# EBN_SBAT_V03A.net
KiCad netlist of a schematic drawn in EAGLE
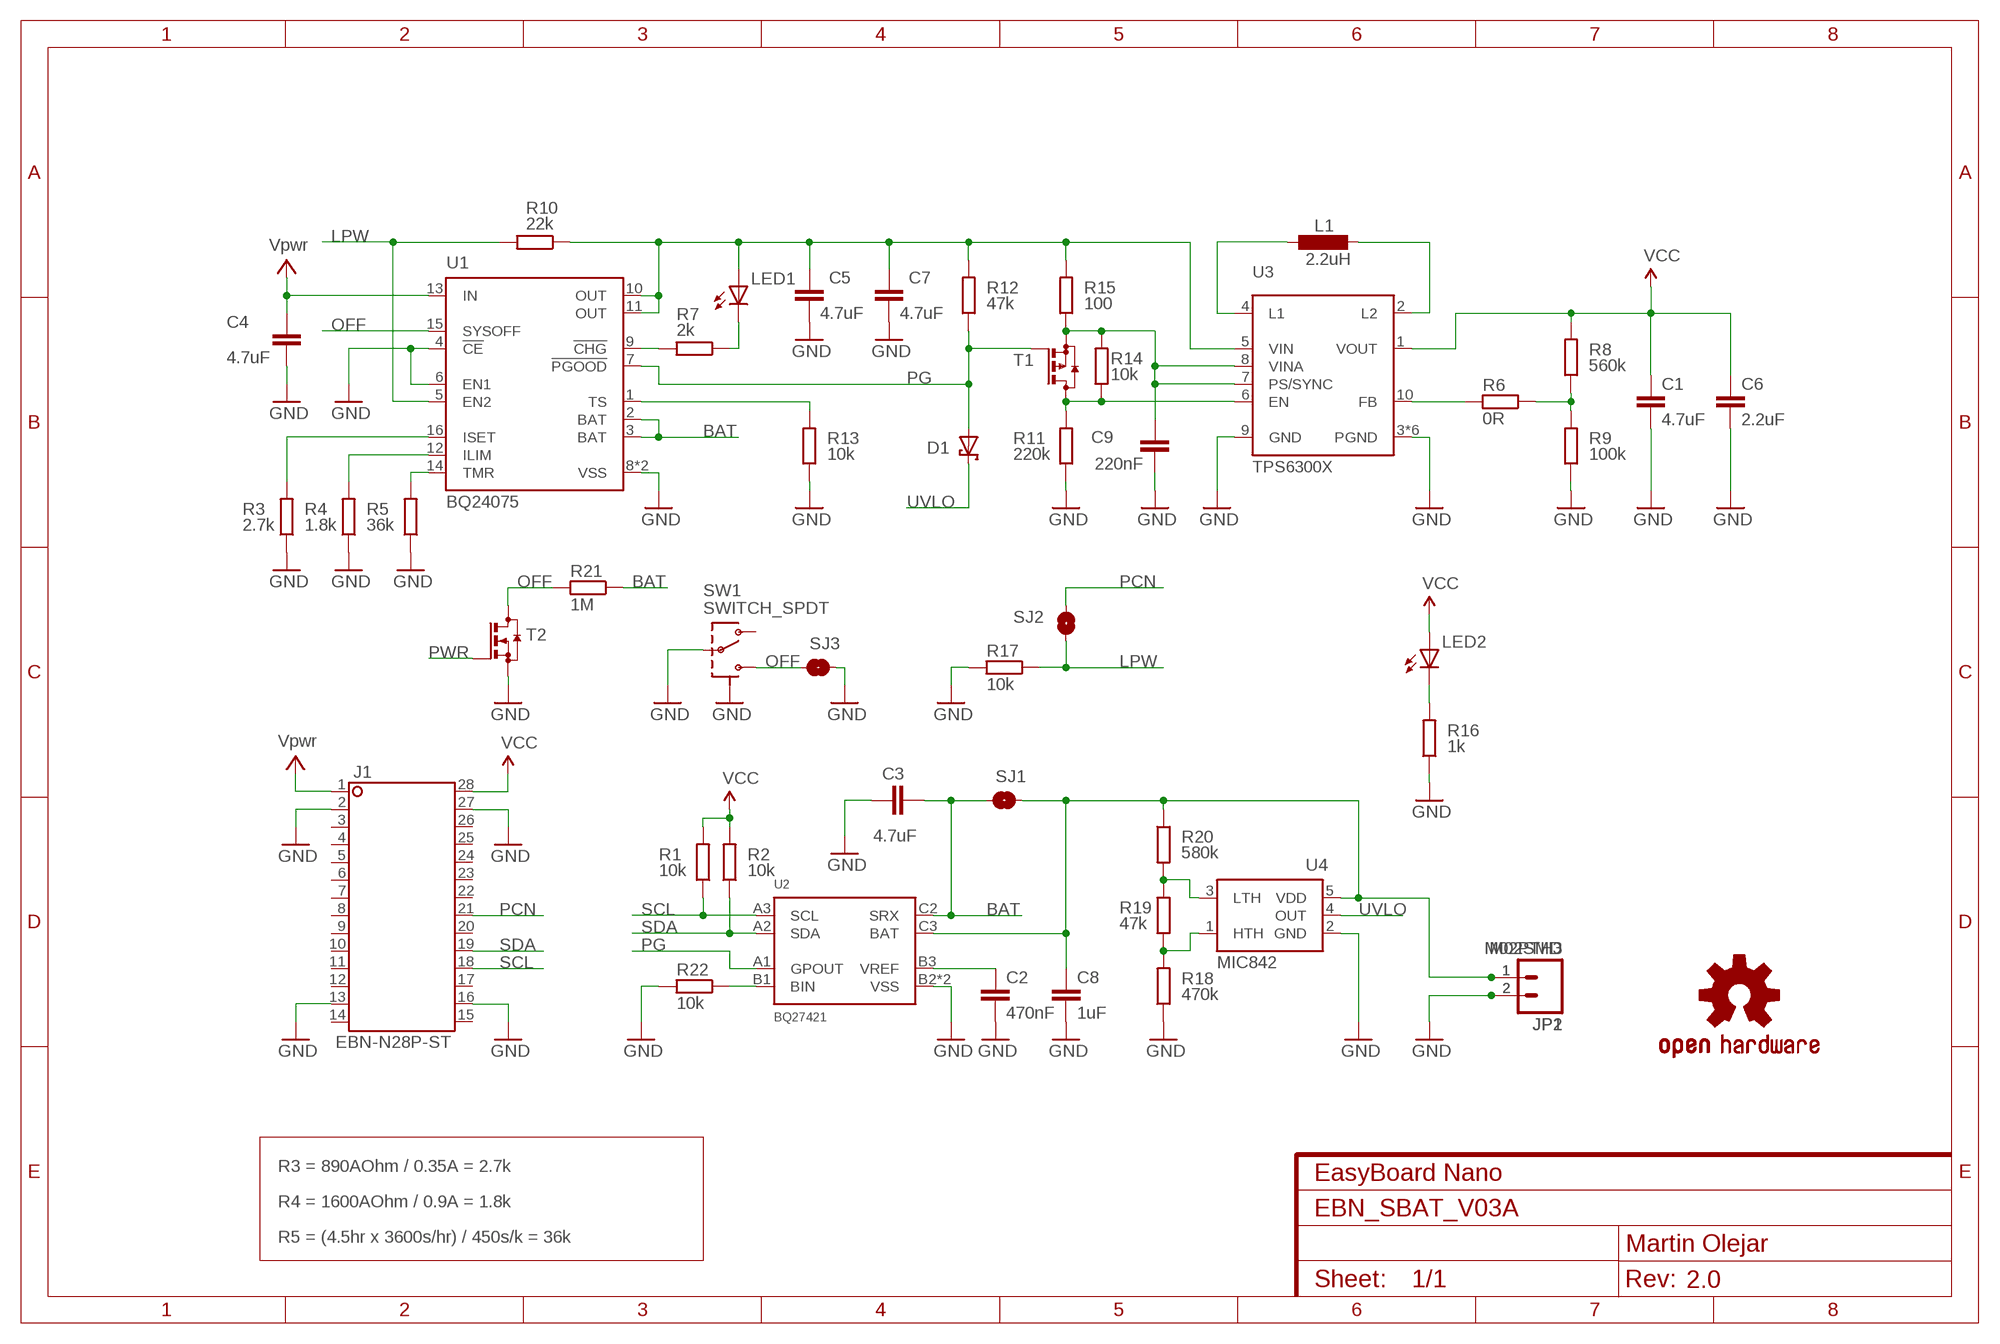
[diagram p0: schematic, sheet 1]

(export (version "E")
  (design (tool "Eeschema 10.0.6"))
  (components
    (comp (ref "C1")
      (value "4.7uF")
      (footprint "eagle-import:C0603")
      (libsource (lib "eagle-import") (part "C-EUC0603"))
    )
    (comp (ref "C2")
      (value "470nF")
      (footprint "eagle-import:C0402")
      (libsource (lib "eagle-import") (part "C-EUC0402"))
    )
    (comp (ref "C3")
      (value "4.7uF")
      (footprint "eagle-import:C0805")
      (libsource (lib "eagle-import") (part "C-EUC0805"))
    )
    (comp (ref "C4")
      (value "4.7uF")
      (footprint "eagle-import:C0603")
      (libsource (lib "eagle-import") (part "C-EUC0603"))
    )
    (comp (ref "C5")
      (value "4.7uF")
      (footprint "eagle-import:C0603")
      (libsource (lib "eagle-import") (part "C-EUC0603"))
    )
    (comp (ref "C6")
      (value "2.2uF")
      (footprint "eagle-import:C0603")
      (libsource (lib "eagle-import") (part "C-EUC0603"))
    )
    (comp (ref "C7")
      (value "4.7uF")
      (footprint "eagle-import:C0603")
      (libsource (lib "eagle-import") (part "C-EUC0603"))
    )
    (comp (ref "C8")
      (value "1uF")
      (footprint "eagle-import:C0402")
      (libsource (lib "eagle-import") (part "C-EUC0402"))
    )
    (comp (ref "C9")
      (value "220nF")
      (footprint "eagle-import:C0402")
      (libsource (lib "eagle-import") (part "C-EUC0402"))
    )
    (comp (ref "D1")
      (value "-SHOTTKY-SOD323_ST")
      (footprint "eagle-import:SOD323_ST")
      (libsource (lib "eagle-import") (part "-SHOTTKY-SOD323_ST"))
    )
    (comp (ref "J1")
      (value "EBN-N28P-ST")
      (footprint "eagle-import:EBN-N28P-SHIELD")
      (libsource (lib "eagle-import") (part "EBN-N28P-ST"))
    )
    (comp (ref "JP1")
      (value "M02SMD")
      (footprint "eagle-import:1X02-1.25MM_SMD")
      (libsource (lib "eagle-import") (part "M02SMD"))
    )
    (comp (ref "JP2")
      (value "M02PTH3")
      (footprint "eagle-import:1X02_LONGPADS")
      (libsource (lib "eagle-import") (part "M02PTH3"))
    )
    (comp (ref "L1")
      (value "2.2uH")
      (footprint "eagle-import:LPS3015")
      (libsource (lib "eagle-import") (part "L-EULPS3015"))
    )
    (comp (ref "LED1")
      (value "LEDCHIPLED_0603")
      (footprint "eagle-import:CHIPLED_0603")
      (libsource (lib "eagle-import") (part "LEDCHIPLED_0603"))
    )
    (comp (ref "LED2")
      (value "LEDCHIPLED_0603")
      (footprint "eagle-import:CHIPLED_0603")
      (libsource (lib "eagle-import") (part "LEDCHIPLED_0603"))
    )
    (comp (ref "LOGO1")
      (value "OSHW-LOGOS")
      (footprint "eagle-import:OSHW-LOGO-S")
      (libsource (lib "eagle-import") (part "OSHW-LOGOS"))
    )
    (comp (ref "R1")
      (value "10k")
      (footprint "eagle-import:R0402")
      (libsource (lib "eagle-import") (part "R-EUR0402"))
    )
    (comp (ref "R2")
      (value "10k")
      (footprint "eagle-import:R0402")
      (libsource (lib "eagle-import") (part "R-EUR0402"))
    )
    (comp (ref "R3")
      (value "2.7k")
      (footprint "eagle-import:R0402")
      (libsource (lib "eagle-import") (part "R-EUR0402"))
    )
    (comp (ref "R4")
      (value "1.8k")
      (footprint "eagle-import:R0402")
      (libsource (lib "eagle-import") (part "R-EUR0402"))
    )
    (comp (ref "R5")
      (value "36k")
      (footprint "eagle-import:R0402")
      (libsource (lib "eagle-import") (part "R-EUR0402"))
    )
    (comp (ref "R6")
      (value "0R")
      (footprint "eagle-import:R0402")
      (libsource (lib "eagle-import") (part "R-EUR0402"))
    )
    (comp (ref "R7")
      (value "2k")
      (footprint "eagle-import:R0402")
      (libsource (lib "eagle-import") (part "R-EUR0402"))
    )
    (comp (ref "R8")
      (value "560k")
      (footprint "eagle-import:R0402")
      (libsource (lib "eagle-import") (part "R-EUR0402"))
    )
    (comp (ref "R9")
      (value "100k")
      (footprint "eagle-import:R0402")
      (libsource (lib "eagle-import") (part "R-EUR0402"))
    )
    (comp (ref "R10")
      (value "22k")
      (footprint "eagle-import:R0402")
      (libsource (lib "eagle-import") (part "R-EUR0402"))
    )
    (comp (ref "R11")
      (value "220k")
      (footprint "eagle-import:R0402")
      (libsource (lib "eagle-import") (part "R-EUR0402"))
    )
    (comp (ref "R12")
      (value "47k")
      (footprint "eagle-import:R0402")
      (libsource (lib "eagle-import") (part "R-EUR0402"))
    )
    (comp (ref "R13")
      (value "10k")
      (footprint "eagle-import:R0402")
      (libsource (lib "eagle-import") (part "R-EUR0402"))
    )
    (comp (ref "R14")
      (value "10k")
      (footprint "eagle-import:R0402")
      (libsource (lib "eagle-import") (part "R-EUR0402"))
    )
    (comp (ref "R15")
      (value "100")
      (footprint "eagle-import:R0402")
      (libsource (lib "eagle-import") (part "R-EUR0402"))
    )
    (comp (ref "R16")
      (value "1k")
      (footprint "eagle-import:R0402")
      (libsource (lib "eagle-import") (part "R-EUR0402"))
    )
    (comp (ref "R17")
      (value "10k")
      (footprint "eagle-import:R0402")
      (libsource (lib "eagle-import") (part "R-EUR0402"))
    )
    (comp (ref "R18")
      (value "470k")
      (footprint "eagle-import:R0402")
      (libsource (lib "eagle-import") (part "R-EUR0402"))
    )
    (comp (ref "R19")
      (value "47k")
      (footprint "eagle-import:R0402")
      (libsource (lib "eagle-import") (part "R-EUR0402"))
    )
    (comp (ref "R20")
      (value "580k")
      (footprint "eagle-import:R0402")
      (libsource (lib "eagle-import") (part "R-EUR0402"))
    )
    (comp (ref "R21")
      (value "1M")
      (footprint "eagle-import:R0402")
      (libsource (lib "eagle-import") (part "R-EUR0402"))
    )
    (comp (ref "R22")
      (value "10k")
      (footprint "eagle-import:R0402")
      (libsource (lib "eagle-import") (part "R-EUR0402"))
    )
    (comp (ref "SJ1")
      (value "SJ-S")
      (footprint "eagle-import:JUMPER-SMD-S1X")
      (libsource (lib "eagle-import") (part "SJ-S"))
    )
    (comp (ref "SJ2")
      (value "SJ-S")
      (footprint "eagle-import:JUMPER-SMD-S1X")
      (libsource (lib "eagle-import") (part "SJ-S"))
    )
    (comp (ref "SJ3")
      (value "SJ-S")
      (footprint "eagle-import:JUMPER-SMD-S1X")
      (libsource (lib "eagle-import") (part "SJ-S"))
    )
    (comp (ref "SW1")
      (value "SWITCH_SPDT")
      (footprint "eagle-import:SWITCH-SPST-SMD-A")
      (libsource (lib "eagle-import") (part "SWITCH_SPDT"))
    )
    (comp (ref "T1")
      (value "-PMOS-SOT323")
      (footprint "eagle-import:SOT323")
      (libsource (lib "eagle-import") (part "-PMOS-SOT323"))
    )
    (comp (ref "T2")
      (value "-NMOS-SOT323")
      (footprint "eagle-import:SOT323")
      (libsource (lib "eagle-import") (part "-NMOS-SOT323"))
    )
    (comp (ref "U1")
      (value "BQ24075")
      (footprint "eagle-import:QFN16-3X3MM")
      (libsource (lib "eagle-import") (part "BQ24075"))
    )
    (comp (ref "U2")
      (value "BQ27421")
      (footprint "eagle-import:XBGA9")
      (libsource (lib "eagle-import") (part "BQ27421"))
    )
    (comp (ref "U3")
      (value "TPS6300X")
      (footprint "eagle-import:QFN-10_PAD")
      (libsource (lib "eagle-import") (part "TPS6300X"))
    )
    (comp (ref "U4")
      (value "MIC842")
      (footprint "eagle-import:SC70")
      (libsource (lib "eagle-import") (part "MIC842"))
    )
  )
  (nets
    (net (code "1") (name "/BAT") (class "Default")
      (node (ref "C3") (pin "1") (pinfunction "1_1") (pintype "passive"))
      (node (ref "R21") (pin "1") (pinfunction "1_1") (pintype "passive"))
      (node (ref "SJ1") (pin "2") (pinfunction "2_2") (pintype "passive"))
      (node (ref "U1") (pin "2") (pinfunction "BAT_2") (pintype "power_in"))
      (node (ref "U1") (pin "3") (pinfunction "BAT_3") (pintype "power_in"))
      (node (ref "U2") (pin "C2") (pinfunction "SRX_C2") (pintype "power_in"))
    )
    (net (code "2") (name "/LPW") (class "Default")
      (node (ref "R10") (pin "2") (pinfunction "2_2") (pintype "passive"))
      (node (ref "R17") (pin "1") (pinfunction "1_1") (pintype "passive"))
      (node (ref "SJ2") (pin "1") (pinfunction "1_1") (pintype "passive"))
      (node (ref "U1") (pin "5") (pinfunction "EN2_5") (pintype "input"))
    )
    (net (code "3") (name "/OFF") (class "Default")
      (node (ref "R21") (pin "2") (pinfunction "2_2") (pintype "passive"))
      (node (ref "SJ3") (pin "1") (pinfunction "1_1") (pintype "passive"))
      (node (ref "SW1") (pin "3") (pinfunction "S_3") (pintype "passive"))
      (node (ref "T2") (pin "3") (pinfunction "D_3") (pintype "passive"))
      (node (ref "U1") (pin "15") (pinfunction "SYSOFF_15") (pintype "input"))
    )
    (net (code "4") (name "/PCN") (class "Default")
      (node (ref "J1") (pin "21") (pinfunction "21_21") (pintype "passive"))
      (node (ref "SJ2") (pin "2") (pinfunction "2_2") (pintype "passive"))
    )
    (net (code "5") (name "/PG") (class "Default")
      (node (ref "D1") (pin "A") (pinfunction "A_A") (pintype "passive"))
      (node (ref "R12") (pin "1") (pinfunction "1_1") (pintype "passive"))
      (node (ref "T1") (pin "1") (pinfunction "G_1") (pintype "passive"))
      (node (ref "U1") (pin "7") (pinfunction "~{PGOOD}_7") (pintype "open_collector"))
      (node (ref "U2") (pin "A1") (pinfunction "GPOUT_A1") (pintype "open_collector"))
    )
    (net (code "6") (name "/SCL") (class "Default")
      (node (ref "J1") (pin "18") (pinfunction "18_18") (pintype "passive"))
      (node (ref "R1") (pin "1") (pinfunction "1_1") (pintype "passive"))
      (node (ref "U2") (pin "A3") (pinfunction "SCL_A3") (pintype "bidirectional"))
    )
    (net (code "7") (name "/SDA") (class "Default")
      (node (ref "J1") (pin "19") (pinfunction "19_19") (pintype "passive"))
      (node (ref "R2") (pin "1") (pinfunction "1_1") (pintype "passive"))
      (node (ref "U2") (pin "A2") (pinfunction "SDA_A2") (pintype "bidirectional"))
    )
    (net (code "8") (name "/UVLO") (class "Default")
      (node (ref "D1") (pin "C") (pinfunction "C_C") (pintype "passive"))
      (node (ref "U4") (pin "4") (pinfunction "OUT_4") (pintype "output"))
    )
    (net (code "9") (name "GND") (class "Default")
      (node (ref "C1") (pin "2") (pinfunction "2_2") (pintype "passive"))
      (node (ref "C2") (pin "1") (pinfunction "1_1") (pintype "passive"))
      (node (ref "C3") (pin "2") (pinfunction "2_2") (pintype "passive"))
      (node (ref "C4") (pin "2") (pinfunction "2_2") (pintype "passive"))
      (node (ref "C5") (pin "2") (pinfunction "2_2") (pintype "passive"))
      (node (ref "C6") (pin "2") (pinfunction "2_2") (pintype "passive"))
      (node (ref "C7") (pin "2") (pinfunction "2_2") (pintype "passive"))
      (node (ref "C8") (pin "1") (pinfunction "1_1") (pintype "passive"))
      (node (ref "C9") (pin "2") (pinfunction "2_2") (pintype "passive"))
      (node (ref "J1") (pin "13") (pinfunction "13_13") (pintype "passive"))
      (node (ref "J1") (pin "16") (pinfunction "16_16") (pintype "passive"))
      (node (ref "J1") (pin "2") (pinfunction "2_2") (pintype "passive"))
      (node (ref "J1") (pin "27") (pinfunction "27_27") (pintype "passive"))
      (node (ref "JP1") (pin "2") (pinfunction "2_2") (pintype "passive"))
      (node (ref "JP2") (pin "2") (pinfunction "2_2") (pintype "passive"))
      (node (ref "R11") (pin "1") (pinfunction "1_1") (pintype "passive"))
      (node (ref "R13") (pin "1") (pinfunction "1_1") (pintype "passive"))
      (node (ref "R16") (pin "1") (pinfunction "1_1") (pintype "passive"))
      (node (ref "R17") (pin "2") (pinfunction "2_2") (pintype "passive"))
      (node (ref "R18") (pin "1") (pinfunction "1_1") (pintype "passive"))
      (node (ref "R22") (pin "2") (pinfunction "2_2") (pintype "passive"))
      (node (ref "R3") (pin "1") (pinfunction "1_1") (pintype "passive"))
      (node (ref "R4") (pin "1") (pinfunction "1_1") (pintype "passive"))
      (node (ref "R5") (pin "1") (pinfunction "1_1") (pintype "passive"))
      (node (ref "R9") (pin "1") (pinfunction "1_1") (pintype "passive"))
      (node (ref "SJ3") (pin "2") (pinfunction "2_2") (pintype "passive"))
      (node (ref "SW1") (pin "2") (pinfunction "P_2") (pintype "passive"))
      (node (ref "SW1") (pin "GND1") (pinfunction "SH_GND1") (pintype "power_in"))
      (node (ref "SW1") (pin "GND2") (pinfunction "SH_GND2") (pintype "power_in"))
      (node (ref "SW1") (pin "GND3") (pinfunction "SH_GND3") (pintype "power_in"))
      (node (ref "SW1") (pin "GND4") (pinfunction "SH_GND4") (pintype "power_in"))
      (node (ref "T2") (pin "2") (pinfunction "S_2") (pintype "passive"))
      (node (ref "U1") (pin "4") (pinfunction "~{CE}_4") (pintype "input"))
      (node (ref "U1") (pin "6") (pinfunction "EN1_6") (pintype "input"))
      (node (ref "U1") (pin "8") (pinfunction "VSS_8") (pintype "power_in"))
      (node (ref "U1") (pin "EXT") (pinfunction "VSS_EXT") (pintype "power_in"))
      (node (ref "U2") (pin "B2") (pinfunction "VSS_B2") (pintype "power_in"))
      (node (ref "U2") (pin "C1") (pinfunction "VSS_C1") (pintype "power_in"))
      (node (ref "U3") (pin "11") (pinfunction "PGND_11") (pintype "power_in"))
      (node (ref "U3") (pin "12") (pinfunction "PGND_12") (pintype "power_in"))
      (node (ref "U3") (pin "13") (pinfunction "PGND_13") (pintype "power_in"))
      (node (ref "U3") (pin "14") (pinfunction "PGND_14") (pintype "power_in"))
      (node (ref "U3") (pin "15") (pinfunction "PGND_15") (pintype "power_in"))
      (node (ref "U3") (pin "3") (pinfunction "PGND_3") (pintype "power_in"))
      (node (ref "U3") (pin "9") (pinfunction "GND_9") (pintype "power_in"))
      (node (ref "U4") (pin "2") (pinfunction "GND_2") (pintype "power_in"))
    )
    (net (code "10") (name "Net-(L1-1)") (class "Default")
      (node (ref "L1") (pin "P$1") (pinfunction "1_P$1") (pintype "passive"))
      (node (ref "U3") (pin "4") (pinfunction "L1_4") (pintype "power_in"))
    )
    (net (code "11") (name "Net-(L1-2)") (class "Default")
      (node (ref "L1") (pin "P$2") (pinfunction "2_P$2") (pintype "passive"))
      (node (ref "U3") (pin "2") (pinfunction "L2_2") (pintype "power_in"))
    )
    (net (code "12") (name "Net-(LED1-PadC)") (class "Default")
      (node (ref "LED1") (pin "C") (pinfunction "C_C") (pintype "passive"))
      (node (ref "R7") (pin "1") (pinfunction "1_1") (pintype "passive"))
    )
    (net (code "13") (name "Net-(LED2-PadC)") (class "Default")
      (node (ref "LED2") (pin "C") (pinfunction "C_C") (pintype "passive"))
      (node (ref "R16") (pin "2") (pinfunction "2_2") (pintype "passive"))
    )
    (net (code "14") (name "Net-(R6-Pad1)") (class "Default")
      (node (ref "R6") (pin "1") (pinfunction "1_1") (pintype "passive"))
      (node (ref "R8") (pin "1") (pinfunction "1_1") (pintype "passive"))
      (node (ref "R9") (pin "2") (pinfunction "2_2") (pintype "passive"))
    )
    (net (code "15") (name "Net-(T1-D)") (class "Default")
      (node (ref "R11") (pin "2") (pinfunction "2_2") (pintype "passive"))
      (node (ref "R14") (pin "1") (pinfunction "1_1") (pintype "passive"))
      (node (ref "T1") (pin "3") (pinfunction "D_3") (pintype "passive"))
      (node (ref "U3") (pin "6") (pinfunction "EN_6") (pintype "power_in"))
    )
    (net (code "16") (name "Net-(T1-S)") (class "Default")
      (node (ref "C9") (pin "1") (pinfunction "1_1") (pintype "passive"))
      (node (ref "R14") (pin "2") (pinfunction "2_2") (pintype "passive"))
      (node (ref "R15") (pin "1") (pinfunction "1_1") (pintype "passive"))
      (node (ref "T1") (pin "2") (pinfunction "S_2") (pintype "passive"))
      (node (ref "U3") (pin "7") (pinfunction "PS/SYNC_7") (pintype "power_in"))
      (node (ref "U3") (pin "8") (pinfunction "VINA_8") (pintype "power_in"))
    )
    (net (code "17") (name "Net-(U1-ILIM)") (class "Default")
      (node (ref "R4") (pin "2") (pinfunction "2_2") (pintype "passive"))
      (node (ref "U1") (pin "12") (pinfunction "ILIM_12") (pintype "input"))
    )
    (net (code "18") (name "Net-(U1-ISET)") (class "Default")
      (node (ref "R3") (pin "2") (pinfunction "2_2") (pintype "passive"))
      (node (ref "U1") (pin "16") (pinfunction "ISET_16") (pintype "input"))
    )
    (net (code "19") (name "Net-(U1-TMR)") (class "Default")
      (node (ref "R5") (pin "2") (pinfunction "2_2") (pintype "passive"))
      (node (ref "U1") (pin "14") (pinfunction "TMR_14") (pintype "input"))
    )
    (net (code "20") (name "Net-(U1-TS)") (class "Default")
      (node (ref "R13") (pin "2") (pinfunction "2_2") (pintype "passive"))
      (node (ref "U1") (pin "1") (pinfunction "TS_1") (pintype "input"))
    )
    (net (code "21") (name "Net-(U1-~{CHG})") (class "Default")
      (node (ref "R7") (pin "2") (pinfunction "2_2") (pintype "passive"))
      (node (ref "U1") (pin "9") (pinfunction "~{CHG}_9") (pintype "open_collector"))
    )
    (net (code "22") (name "Net-(U2-BAT)") (class "Default")
      (node (ref "C8") (pin "2") (pinfunction "2_2") (pintype "passive"))
      (node (ref "JP1") (pin "1") (pinfunction "1_1") (pintype "passive"))
      (node (ref "JP2") (pin "1") (pinfunction "1_1") (pintype "passive"))
      (node (ref "R20") (pin "1") (pinfunction "1_1") (pintype "passive"))
      (node (ref "SJ1") (pin "1") (pinfunction "1_1") (pintype "passive"))
      (node (ref "U2") (pin "C3") (pinfunction "BAT_C3") (pintype "power_in"))
      (node (ref "U4") (pin "5") (pinfunction "VDD_5") (pintype "power_in"))
    )
    (net (code "23") (name "Net-(U2-BIN)") (class "Default")
      (node (ref "R22") (pin "1") (pinfunction "1_1") (pintype "passive"))
      (node (ref "U2") (pin "B1") (pinfunction "BIN_B1") (pintype "bidirectional"))
    )
    (net (code "24") (name "Net-(U2-VREF)") (class "Default")
      (node (ref "C2") (pin "2") (pinfunction "2_2") (pintype "passive"))
      (node (ref "U2") (pin "B3") (pinfunction "VREF_B3") (pintype "power_in"))
    )
    (net (code "25") (name "Net-(U3-FB)") (class "Default")
      (node (ref "R6") (pin "2") (pinfunction "2_2") (pintype "passive"))
      (node (ref "U3") (pin "10") (pinfunction "FB_10") (pintype "input"))
    )
    (net (code "26") (name "Net-(U3-VIN)") (class "Default")
      (node (ref "C5") (pin "1") (pinfunction "1_1") (pintype "passive"))
      (node (ref "C7") (pin "1") (pinfunction "1_1") (pintype "passive"))
      (node (ref "LED1") (pin "A") (pinfunction "A_A") (pintype "passive"))
      (node (ref "R10") (pin "1") (pinfunction "1_1") (pintype "passive"))
      (node (ref "R12") (pin "2") (pinfunction "2_2") (pintype "passive"))
      (node (ref "R15") (pin "2") (pinfunction "2_2") (pintype "passive"))
      (node (ref "U1") (pin "10") (pinfunction "OUT_10") (pintype "power_in"))
      (node (ref "U1") (pin "11") (pinfunction "OUT_11") (pintype "power_in"))
      (node (ref "U3") (pin "5") (pinfunction "VIN_5") (pintype "power_in"))
    )
    (net (code "27") (name "Net-(U4-HTH)") (class "Default")
      (node (ref "R18") (pin "2") (pinfunction "2_2") (pintype "passive"))
      (node (ref "R19") (pin "1") (pinfunction "1_1") (pintype "passive"))
      (node (ref "U4") (pin "1") (pinfunction "HTH_1") (pintype "input"))
    )
    (net (code "28") (name "Net-(U4-LTH)") (class "Default")
      (node (ref "R19") (pin "2") (pinfunction "2_2") (pintype "passive"))
      (node (ref "R20") (pin "2") (pinfunction "2_2") (pintype "passive"))
      (node (ref "U4") (pin "3") (pinfunction "LTH_3") (pintype "input"))
    )
    (net (code "29") (name "VCC") (class "Default")
      (node (ref "C1") (pin "1") (pinfunction "1_1") (pintype "passive"))
      (node (ref "C6") (pin "1") (pinfunction "1_1") (pintype "passive"))
      (node (ref "J1") (pin "28") (pinfunction "28_28") (pintype "passive"))
      (node (ref "LED2") (pin "A") (pinfunction "A_A") (pintype "passive"))
      (node (ref "R1") (pin "2") (pinfunction "2_2") (pintype "passive"))
      (node (ref "R2") (pin "2") (pinfunction "2_2") (pintype "passive"))
      (node (ref "R8") (pin "2") (pinfunction "2_2") (pintype "passive"))
      (node (ref "U3") (pin "1") (pinfunction "VOUT_1") (pintype "output"))
    )
    (net (code "30") (name "Vpwr") (class "Default")
      (node (ref "C4") (pin "1") (pinfunction "1_1") (pintype "passive"))
      (node (ref "J1") (pin "1") (pinfunction "1_1") (pintype "passive"))
      (node (ref "T2") (pin "1") (pinfunction "G_1") (pintype "passive"))
      (node (ref "U1") (pin "13") (pinfunction "IN_13") (pintype "power_in"))
    )
    (net (code "31") (name "unconnected-(J1-Pad3)") (class "Default")
      (node (ref "J1") (pin "3") (pinfunction "3_3") (pintype "passive"))
    )
    (net (code "32") (name "unconnected-(J1-Pad4)") (class "Default")
      (node (ref "J1") (pin "4") (pinfunction "4_4") (pintype "passive"))
    )
    (net (code "33") (name "unconnected-(J1-Pad5)") (class "Default")
      (node (ref "J1") (pin "5") (pinfunction "5_5") (pintype "passive"))
    )
    (net (code "34") (name "unconnected-(J1-Pad6)") (class "Default")
      (node (ref "J1") (pin "6") (pinfunction "6_6") (pintype "passive"))
    )
    (net (code "35") (name "unconnected-(J1-Pad7)") (class "Default")
      (node (ref "J1") (pin "7") (pinfunction "7_7") (pintype "passive"))
    )
    (net (code "36") (name "unconnected-(J1-Pad8)") (class "Default")
      (node (ref "J1") (pin "8") (pinfunction "8_8") (pintype "passive"))
    )
    (net (code "37") (name "unconnected-(J1-Pad9)") (class "Default")
      (node (ref "J1") (pin "9") (pinfunction "9_9") (pintype "passive"))
    )
    (net (code "38") (name "unconnected-(J1-Pad10)") (class "Default")
      (node (ref "J1") (pin "10") (pinfunction "10_10") (pintype "passive"))
    )
    (net (code "39") (name "unconnected-(J1-Pad11)") (class "Default")
      (node (ref "J1") (pin "11") (pinfunction "11_11") (pintype "passive"))
    )
    (net (code "40") (name "unconnected-(J1-Pad12)") (class "Default")
      (node (ref "J1") (pin "12") (pinfunction "12_12") (pintype "passive"))
    )
    (net (code "41") (name "unconnected-(J1-Pad14)") (class "Default")
      (node (ref "J1") (pin "14") (pinfunction "14_14") (pintype "passive"))
    )
    (net (code "42") (name "unconnected-(J1-Pad15)") (class "Default")
      (node (ref "J1") (pin "15") (pinfunction "15_15") (pintype "passive"))
    )
    (net (code "43") (name "unconnected-(J1-Pad17)") (class "Default")
      (node (ref "J1") (pin "17") (pinfunction "17_17") (pintype "passive"))
    )
    (net (code "44") (name "unconnected-(J1-Pad20)") (class "Default")
      (node (ref "J1") (pin "20") (pinfunction "20_20") (pintype "passive"))
    )
    (net (code "45") (name "unconnected-(J1-Pad22)") (class "Default")
      (node (ref "J1") (pin "22") (pinfunction "22_22") (pintype "passive"))
    )
    (net (code "46") (name "unconnected-(J1-Pad23)") (class "Default")
      (node (ref "J1") (pin "23") (pinfunction "23_23") (pintype "passive"))
    )
    (net (code "47") (name "unconnected-(J1-Pad24)") (class "Default")
      (node (ref "J1") (pin "24") (pinfunction "24_24") (pintype "passive"))
    )
    (net (code "48") (name "unconnected-(J1-Pad25)") (class "Default")
      (node (ref "J1") (pin "25") (pinfunction "25_25") (pintype "passive"))
    )
    (net (code "49") (name "unconnected-(J1-Pad26)") (class "Default")
      (node (ref "J1") (pin "26") (pinfunction "26_26") (pintype "passive"))
    )
    (net (code "50") (name "unconnected-(SW1-O-Pad1)") (class "Default")
      (node (ref "SW1") (pin "1") (pinfunction "O_1") (pintype "passive"))
    )
  )
)
